# LiquidLevelSwitch.net
KiCad netlist of a schematic drawn in EAGLE
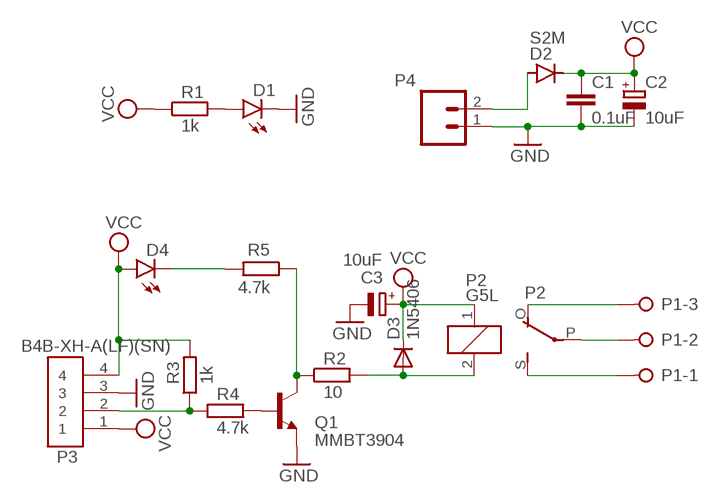
[diagram p0: schematic, sheet 1]

(export (version "E")
  (design (tool "Eeschema 10.0.6"))
  (components
    (comp (ref "C1")
      (value "0.1uF")
      (footprint "eagle-import:C0805")
      (libsource (lib "eagle-import") (part "C-EUC0805"))
    )
    (comp (ref "C2")
      (value "10uF")
      (footprint "eagle-import:B_3528-21R")
      (libsource (lib "eagle-import") (part "CPOL-EUB/3528-21R"))
    )
    (comp (ref "C3")
      (value "10uF")
      (footprint "eagle-import:B_3528-21R")
      (libsource (lib "eagle-import") (part "CPOL-EUB/3528-21R"))
    )
    (comp (ref "D1")
      (value "LEDCHIP-LED0805")
      (footprint "eagle-import:CHIP-LED0805")
      (libsource (lib "eagle-import") (part "LEDCHIP-LED0805"))
    )
    (comp (ref "D2")
      (value "S2M")
      (footprint "eagle-import:DO214AC")
      (libsource (lib "eagle-import") (part "DIODE-DO214AC"))
    )
    (comp (ref "D3")
      (value "1N5406")
      (footprint "eagle-import:SMADIODE")
      (libsource (lib "eagle-import") (part "DIODESMA"))
    )
    (comp (ref "D4")
      (value "LEDCHIP-LED0805")
      (footprint "eagle-import:CHIP-LED0805")
      (libsource (lib "eagle-import") (part "LEDCHIP-LED0805"))
    )
    (comp (ref "P1")
      (value "W237-03P")
      (footprint "eagle-import:W237-133")
      (libsource (lib "eagle-import") (part "W237-03P"))
    )
    (comp (ref "P2")
      (value "G5L")
      (footprint "eagle-import:G5LE")
      (libsource (lib "eagle-import") (part "G5L"))
    )
    (comp (ref "P3")
      (value "B4B-XH-A(LF)(SN)")
      (footprint "eagle-import:JST_B4B-XH-A(LF)(SN)")
      (fields (field (name "MF") "JST Sales"))
      (libsource (lib "eagle-import") (part "B4B-XH-A(LF)(SN)"))
    )
    (comp (ref "P4")
      (value "CONN_02")
      (footprint "eagle-import:1X02")
      (libsource (lib "eagle-import") (part "CONN_02"))
    )
    (comp (ref "Q1")
      (value "MMBT3904")
      (footprint "eagle-import:SOT23-BEC")
      (libsource (lib "eagle-import") (part "-NPN-SOT23-BECMMBT3904LT1"))
    )
    (comp (ref "R1")
      (value "1k")
      (footprint "eagle-import:R0805")
      (libsource (lib "eagle-import") (part "R-EU_R0805"))
    )
    (comp (ref "R2")
      (value "10")
      (footprint "eagle-import:R0805")
      (libsource (lib "eagle-import") (part "R-EU_R0805"))
    )
    (comp (ref "R3")
      (value "1k")
      (footprint "eagle-import:R0805")
      (libsource (lib "eagle-import") (part "R-EU_R0805"))
    )
    (comp (ref "R4")
      (value "4.7k")
      (footprint "eagle-import:R0805")
      (libsource (lib "eagle-import") (part "R-EU_R0805"))
    )
    (comp (ref "R5")
      (value "4.7k")
      (footprint "eagle-import:R0805")
      (libsource (lib "eagle-import") (part "R-EU_R0805"))
    )
  )
  (nets
    (net (code "1") (name "GND") (class "Default")
      (node (ref "C1") (pin "2") (pinfunction "2_2") (pintype "passive"))
      (node (ref "C2") (pin "-") (pinfunction "-_-") (pintype "passive"))
      (node (ref "C3") (pin "-") (pinfunction "-_-") (pintype "passive"))
      (node (ref "D1") (pin "C") (pinfunction "C_C") (pintype "passive"))
      (node (ref "P3") (pin "3") (pinfunction "3_3") (pintype "passive"))
      (node (ref "P4") (pin "1") (pinfunction "1_1") (pintype "passive"))
      (node (ref "Q1") (pin "E") (pinfunction "E_E") (pintype "passive"))
    )
    (net (code "2") (name "Net-(D1-PadA)") (class "Default")
      (node (ref "D1") (pin "A") (pinfunction "A_A") (pintype "passive"))
      (node (ref "R1") (pin "2") (pinfunction "2_2") (pintype "passive"))
    )
    (net (code "3") (name "Net-(D2-PadA)") (class "Default")
      (node (ref "D2") (pin "A") (pinfunction "A_A") (pintype "passive"))
      (node (ref "P4") (pin "2") (pinfunction "2_2") (pintype "passive"))
    )
    (net (code "4") (name "Net-(D3-PadA)") (class "Default")
      (node (ref "D3") (pin "A") (pinfunction "A_A") (pintype "passive"))
      (node (ref "P2") (pin "2") (pinfunction "2_2") (pintype "passive"))
      (node (ref "R2") (pin "2") (pinfunction "2_2") (pintype "passive"))
    )
    (net (code "5") (name "Net-(D4-PadC)") (class "Default")
      (node (ref "D4") (pin "C") (pinfunction "C_C") (pintype "passive"))
      (node (ref "R5") (pin "2") (pinfunction "2_2") (pintype "passive"))
    )
    (net (code "6") (name "Net-(P1A-KL)") (class "Default")
      (node (ref "P1") (pin "1") (pinfunction "KL_1") (pintype "passive"))
      (node (ref "P2") (pin "S") (pinfunction "S_S") (pintype "passive"))
    )
    (net (code "7") (name "Net-(P1B-KL)") (class "Default")
      (node (ref "P1") (pin "2") (pinfunction "KL_2") (pintype "passive"))
      (node (ref "P2") (pin "P") (pinfunction "P_P") (pintype "passive"))
    )
    (net (code "8") (name "Net-(P1C-KL)") (class "Default")
      (node (ref "P1") (pin "3") (pinfunction "KL_3") (pintype "passive"))
      (node (ref "P2") (pin "O") (pinfunction "O_O") (pintype "passive"))
    )
    (net (code "9") (name "Net-(P3-Pad2)") (class "Default")
      (node (ref "P3") (pin "2") (pinfunction "2_2") (pintype "passive"))
      (node (ref "R3") (pin "1") (pinfunction "1_1") (pintype "passive"))
      (node (ref "R4") (pin "1") (pinfunction "1_1") (pintype "passive"))
    )
    (net (code "10") (name "Net-(Q1-PadB)") (class "Default")
      (node (ref "Q1") (pin "B") (pinfunction "B_B") (pintype "passive"))
      (node (ref "R4") (pin "2") (pinfunction "2_2") (pintype "passive"))
    )
    (net (code "11") (name "Net-(Q1-PadC)") (class "Default")
      (node (ref "Q1") (pin "C") (pinfunction "C_C") (pintype "passive"))
      (node (ref "R2") (pin "1") (pinfunction "1_1") (pintype "passive"))
      (node (ref "R5") (pin "1") (pinfunction "1_1") (pintype "passive"))
    )
    (net (code "12") (name "VCC") (class "Default")
      (node (ref "C1") (pin "1") (pinfunction "1_1") (pintype "passive"))
      (node (ref "C2") (pin "+") (pinfunction "+_+") (pintype "passive"))
      (node (ref "C3") (pin "+") (pinfunction "+_+") (pintype "passive"))
      (node (ref "D2") (pin "C") (pinfunction "C_C") (pintype "passive"))
      (node (ref "D3") (pin "C") (pinfunction "C_C") (pintype "passive"))
      (node (ref "D4") (pin "A") (pinfunction "A_A") (pintype "passive"))
      (node (ref "P2") (pin "1") (pinfunction "1_1") (pintype "passive"))
      (node (ref "P3") (pin "1") (pinfunction "1_1") (pintype "passive"))
      (node (ref "P3") (pin "4") (pinfunction "4_4") (pintype "passive"))
      (node (ref "R1") (pin "1") (pinfunction "1_1") (pintype "passive"))
      (node (ref "R3") (pin "2") (pinfunction "2_2") (pintype "passive"))
    )
  )
)
